# HALL_SENSOR_BOARD.net
KiCad netlist of a schematic drawn in Altium Designer
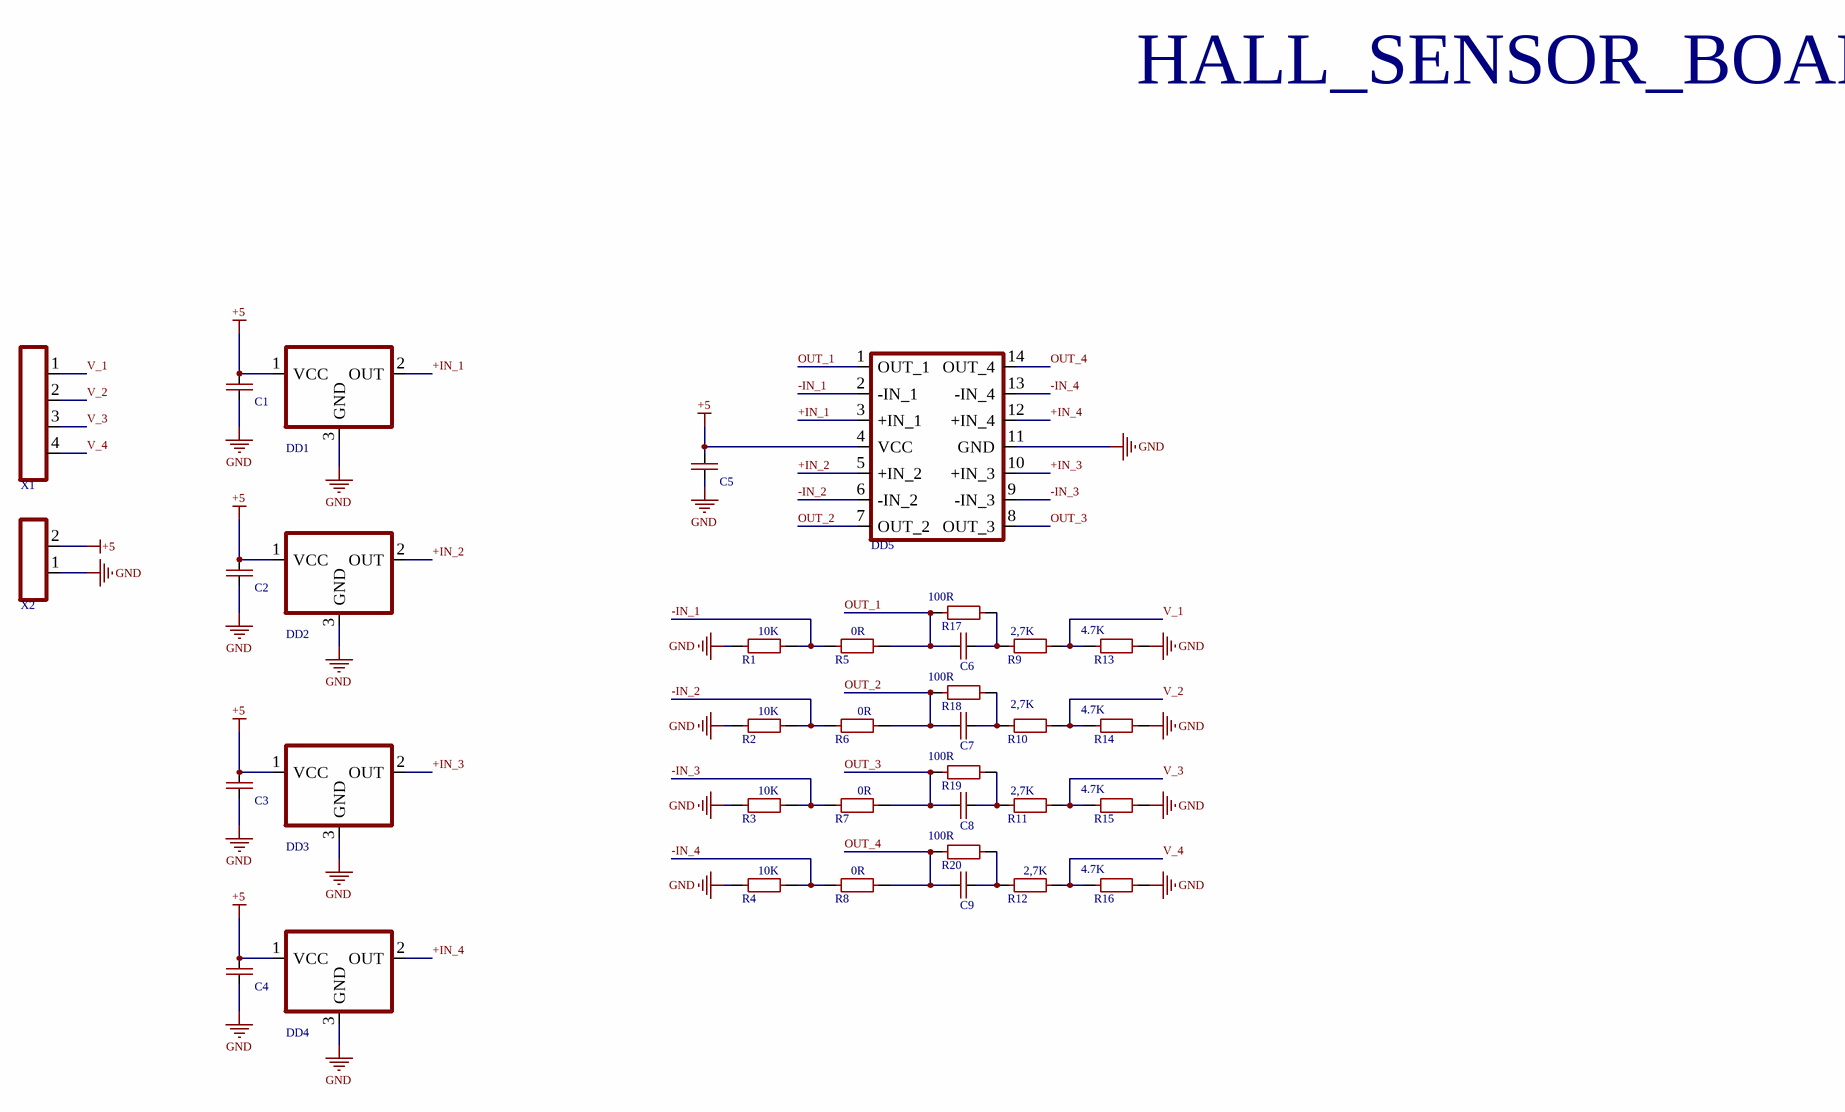
[diagram p0: HALL_SENSOR_BOARD.SchDoc]

(export (version "E")
  (design (tool "Eeschema 10.0.6"))
  (components
    (comp (ref "C1")
      (value "CAP-NON-POLAR")
      (footprint "CAP-0805")
      (libsource (lib "PASSIVE_COMPONENTS") (part "CAP-NON-POLAR"))
    )
    (comp (ref "C2")
      (value "CAP-NON-POLAR")
      (footprint "CAP-0805")
      (libsource (lib "PASSIVE_COMPONENTS") (part "CAP-NON-POLAR"))
    )
    (comp (ref "C3")
      (value "CAP-NON-POLAR")
      (footprint "CAP-0805")
      (libsource (lib "PASSIVE_COMPONENTS") (part "CAP-NON-POLAR"))
    )
    (comp (ref "C4")
      (value "CAP-NON-POLAR")
      (footprint "CAP-0805")
      (libsource (lib "PASSIVE_COMPONENTS") (part "CAP-NON-POLAR"))
    )
    (comp (ref "C5")
      (value "CAP-NON-POLAR")
      (footprint "CAP-0805")
      (libsource (lib "PASSIVE_COMPONENTS") (part "CAP-NON-POLAR"))
    )
    (comp (ref "C6")
      (value "CAP-NON-POLAR")
      (footprint "CAP-0805")
      (libsource (lib "PASSIVE_COMPONENTS") (part "CAP-NON-POLAR"))
    )
    (comp (ref "C7")
      (value "CAP-NON-POLAR")
      (footprint "CAP-0805")
      (libsource (lib "PASSIVE_COMPONENTS") (part "CAP-NON-POLAR"))
    )
    (comp (ref "C8")
      (value "CAP-NON-POLAR")
      (footprint "CAP-0805")
      (libsource (lib "PASSIVE_COMPONENTS") (part "CAP-NON-POLAR"))
    )
    (comp (ref "C9")
      (value "CAP-NON-POLAR")
      (footprint "CAP-0805")
      (libsource (lib "PASSIVE_COMPONENTS") (part "CAP-NON-POLAR"))
    )
    (comp (ref "DD1") (value "49E") (footprint "SOT23-3") (libsource (lib "49E") (part "49E")))
    (comp (ref "DD2") (value "49E") (footprint "SOT23-3") (libsource (lib "49E") (part "49E")))
    (comp (ref "DD3") (value "49E") (footprint "SOT23-3") (libsource (lib "49E") (part "49E")))
    (comp (ref "DD4") (value "49E") (footprint "SOT23-3") (libsource (lib "49E") (part "49E")))
    (comp (ref "DD5") (value "LM324") (footprint "SOIC14") (libsource (lib "LM324") (part "LM324")))
    (comp (ref "R1")
      (value "10K")
      (footprint "RES-0603")
      (libsource (lib "PASSIVE_COMPONENTS") (part "RES-CONST"))
    )
    (comp (ref "R2")
      (value "10K")
      (footprint "RES-0603")
      (libsource (lib "PASSIVE_COMPONENTS") (part "RES-CONST"))
    )
    (comp (ref "R3")
      (value "10K")
      (footprint "RES-0603")
      (libsource (lib "PASSIVE_COMPONENTS") (part "RES-CONST"))
    )
    (comp (ref "R4")
      (value "10K")
      (footprint "RES-0603")
      (libsource (lib "PASSIVE_COMPONENTS") (part "RES-CONST"))
    )
    (comp (ref "R5")
      (value "0R")
      (footprint "RES-0603")
      (libsource (lib "PASSIVE_COMPONENTS") (part "RES-CONST"))
    )
    (comp (ref "R6")
      (value "0R")
      (footprint "RES-0603")
      (libsource (lib "PASSIVE_COMPONENTS") (part "RES-CONST"))
    )
    (comp (ref "R7")
      (value "0R")
      (footprint "RES-0603")
      (libsource (lib "PASSIVE_COMPONENTS") (part "RES-CONST"))
    )
    (comp (ref "R8")
      (value "0R")
      (footprint "RES-0603")
      (libsource (lib "PASSIVE_COMPONENTS") (part "RES-CONST"))
    )
    (comp (ref "R9")
      (value "2,7K")
      (footprint "RES-0603")
      (libsource (lib "PASSIVE_COMPONENTS") (part "RES-CONST"))
    )
    (comp (ref "R10")
      (value "2,7K")
      (footprint "RES-0603")
      (libsource (lib "PASSIVE_COMPONENTS") (part "RES-CONST"))
    )
    (comp (ref "R11")
      (value "2,7K")
      (footprint "RES-0603")
      (libsource (lib "PASSIVE_COMPONENTS") (part "RES-CONST"))
    )
    (comp (ref "R12")
      (value "2,7K")
      (footprint "RES-0603")
      (libsource (lib "PASSIVE_COMPONENTS") (part "RES-CONST"))
    )
    (comp (ref "R13")
      (value "4.7K")
      (footprint "RES-0603")
      (libsource (lib "PASSIVE_COMPONENTS") (part "RES-CONST"))
    )
    (comp (ref "R14")
      (value "4.7K")
      (footprint "RES-0603")
      (libsource (lib "PASSIVE_COMPONENTS") (part "RES-CONST"))
    )
    (comp (ref "R15")
      (value "4.7K")
      (footprint "RES-0603")
      (libsource (lib "PASSIVE_COMPONENTS") (part "RES-CONST"))
    )
    (comp (ref "R16")
      (value "4.7K")
      (footprint "RES-0603")
      (libsource (lib "PASSIVE_COMPONENTS") (part "RES-CONST"))
    )
    (comp (ref "R17")
      (value "100R")
      (footprint "RES-0603")
      (libsource (lib "PASSIVE_COMPONENTS") (part "RES-CONST"))
    )
    (comp (ref "R18")
      (value "100R")
      (footprint "RES-0603")
      (libsource (lib "PASSIVE_COMPONENTS") (part "RES-CONST"))
    )
    (comp (ref "R19")
      (value "100R")
      (footprint "RES-0603")
      (libsource (lib "PASSIVE_COMPONENTS") (part "RES-CONST"))
    )
    (comp (ref "R20")
      (value "100R")
      (footprint "RES-0603")
      (libsource (lib "PASSIVE_COMPONENTS") (part "RES-CONST"))
    )
    (comp (ref "X1")
      (value "CONN-4-PIN")
      (footprint "CONN-PLS-4-2.54mm")
      (libsource (lib "CONNECTORS") (part "CONN-4-PIN"))
    )
    (comp (ref "X2")
      (value "CONN-2-PIN")
      (footprint "CONN-PLS-2-2.54mm")
      (libsource (lib "CONNECTORS") (part "CONN-2-PIN"))
    )
  )
  (nets
    (net (code "1") (name "+5") (class "Default")
      (node (ref "C1") (pin "2") (pinfunction "2_2") (pintype "passive"))
      (node (ref "C2") (pin "2") (pinfunction "2_2") (pintype "passive"))
      (node (ref "C3") (pin "2") (pinfunction "2_2") (pintype "passive"))
      (node (ref "C4") (pin "2") (pinfunction "2_2") (pintype "passive"))
      (node (ref "C5") (pin "2") (pinfunction "2_2") (pintype "passive"))
      (node (ref "DD1") (pin "1") (pinfunction "VCC_1") (pintype "passive"))
      (node (ref "DD2") (pin "1") (pinfunction "VCC_1") (pintype "passive"))
      (node (ref "DD3") (pin "1") (pinfunction "VCC_1") (pintype "passive"))
      (node (ref "DD4") (pin "1") (pinfunction "VCC_1") (pintype "passive"))
      (node (ref "DD5") (pin "4") (pinfunction "VCC_4") (pintype "passive"))
      (node (ref "X2") (pin "2") (pinfunction "2_2") (pintype "passive"))
    )
    (net (code "2") (name "/+IN_1") (class "Default")
      (node (ref "DD1") (pin "2") (pinfunction "OUT_2") (pintype "passive"))
      (node (ref "DD5") (pin "3") (pinfunction "+IN_1_3") (pintype "passive"))
    )
    (net (code "3") (name "/+IN_2") (class "Default")
      (node (ref "DD2") (pin "2") (pinfunction "OUT_2") (pintype "passive"))
      (node (ref "DD5") (pin "5") (pinfunction "+IN_2_5") (pintype "passive"))
    )
    (net (code "4") (name "/+IN_3") (class "Default")
      (node (ref "DD3") (pin "2") (pinfunction "OUT_2") (pintype "passive"))
      (node (ref "DD5") (pin "10") (pinfunction "+IN_3_10") (pintype "passive"))
    )
    (net (code "5") (name "/+IN_4") (class "Default")
      (node (ref "DD4") (pin "2") (pinfunction "OUT_2") (pintype "passive"))
      (node (ref "DD5") (pin "12") (pinfunction "+IN_4_12") (pintype "passive"))
    )
    (net (code "6") (name "/-IN_1") (class "Default")
      (node (ref "DD5") (pin "2") (pinfunction "-IN_1_2") (pintype "passive"))
      (node (ref "R1") (pin "2") (pinfunction "2_2") (pintype "passive"))
      (node (ref "R5") (pin "1") (pinfunction "1_1") (pintype "passive"))
    )
    (net (code "7") (name "/-IN_2") (class "Default")
      (node (ref "DD5") (pin "6") (pinfunction "-IN_2_6") (pintype "passive"))
      (node (ref "R2") (pin "2") (pinfunction "2_2") (pintype "passive"))
      (node (ref "R6") (pin "1") (pinfunction "1_1") (pintype "passive"))
    )
    (net (code "8") (name "/-IN_3") (class "Default")
      (node (ref "DD5") (pin "9") (pinfunction "-IN_3_9") (pintype "passive"))
      (node (ref "R3") (pin "2") (pinfunction "2_2") (pintype "passive"))
      (node (ref "R7") (pin "1") (pinfunction "1_1") (pintype "passive"))
    )
    (net (code "9") (name "/-IN_4") (class "Default")
      (node (ref "DD5") (pin "13") (pinfunction "-IN_4_13") (pintype "passive"))
      (node (ref "R4") (pin "2") (pinfunction "2_2") (pintype "passive"))
      (node (ref "R8") (pin "1") (pinfunction "1_1") (pintype "passive"))
    )
    (net (code "10") (name "/OUT_1") (class "Default")
      (node (ref "C6") (pin "2") (pinfunction "2_2") (pintype "passive"))
      (node (ref "DD5") (pin "1") (pinfunction "OUT_1_1") (pintype "passive"))
      (node (ref "R17") (pin "2") (pinfunction "2_2") (pintype "passive"))
      (node (ref "R5") (pin "2") (pinfunction "2_2") (pintype "passive"))
    )
    (net (code "11") (name "/OUT_2") (class "Default")
      (node (ref "C7") (pin "2") (pinfunction "2_2") (pintype "passive"))
      (node (ref "DD5") (pin "7") (pinfunction "OUT_2_7") (pintype "passive"))
      (node (ref "R18") (pin "2") (pinfunction "2_2") (pintype "passive"))
      (node (ref "R6") (pin "2") (pinfunction "2_2") (pintype "passive"))
    )
    (net (code "12") (name "/OUT_3") (class "Default")
      (node (ref "C8") (pin "2") (pinfunction "2_2") (pintype "passive"))
      (node (ref "DD5") (pin "8") (pinfunction "OUT_3_8") (pintype "passive"))
      (node (ref "R19") (pin "2") (pinfunction "2_2") (pintype "passive"))
      (node (ref "R7") (pin "2") (pinfunction "2_2") (pintype "passive"))
    )
    (net (code "13") (name "/OUT_4") (class "Default")
      (node (ref "C9") (pin "2") (pinfunction "2_2") (pintype "passive"))
      (node (ref "DD5") (pin "14") (pinfunction "OUT_4_14") (pintype "passive"))
      (node (ref "R20") (pin "2") (pinfunction "2_2") (pintype "passive"))
      (node (ref "R8") (pin "2") (pinfunction "2_2") (pintype "passive"))
    )
    (net (code "14") (name "/V_1") (class "Default")
      (node (ref "R13") (pin "2") (pinfunction "2_2") (pintype "passive"))
      (node (ref "R9") (pin "1") (pinfunction "1_1") (pintype "passive"))
      (node (ref "X1") (pin "1") (pinfunction "1_1") (pintype "passive"))
    )
    (net (code "15") (name "/V_2") (class "Default")
      (node (ref "R10") (pin "1") (pinfunction "1_1") (pintype "passive"))
      (node (ref "R14") (pin "2") (pinfunction "2_2") (pintype "passive"))
      (node (ref "X1") (pin "2") (pinfunction "2_2") (pintype "passive"))
    )
    (net (code "16") (name "/V_3") (class "Default")
      (node (ref "R11") (pin "1") (pinfunction "1_1") (pintype "passive"))
      (node (ref "R15") (pin "2") (pinfunction "2_2") (pintype "passive"))
      (node (ref "X1") (pin "3") (pinfunction "3_3") (pintype "passive"))
    )
    (net (code "17") (name "/V_4") (class "Default")
      (node (ref "R12") (pin "1") (pinfunction "1_1") (pintype "passive"))
      (node (ref "R16") (pin "2") (pinfunction "2_2") (pintype "passive"))
      (node (ref "X1") (pin "4") (pinfunction "4_4") (pintype "passive"))
    )
    (net (code "18") (name "GND") (class "Default")
      (node (ref "C1") (pin "1") (pinfunction "1_1") (pintype "passive"))
      (node (ref "C2") (pin "1") (pinfunction "1_1") (pintype "passive"))
      (node (ref "C3") (pin "1") (pinfunction "1_1") (pintype "passive"))
      (node (ref "C4") (pin "1") (pinfunction "1_1") (pintype "passive"))
      (node (ref "C5") (pin "1") (pinfunction "1_1") (pintype "passive"))
      (node (ref "DD1") (pin "3") (pinfunction "GND_3") (pintype "passive"))
      (node (ref "DD2") (pin "3") (pinfunction "GND_3") (pintype "passive"))
      (node (ref "DD3") (pin "3") (pinfunction "GND_3") (pintype "passive"))
      (node (ref "DD4") (pin "3") (pinfunction "GND_3") (pintype "passive"))
      (node (ref "DD5") (pin "11") (pinfunction "GND_11") (pintype "passive"))
      (node (ref "R1") (pin "1") (pinfunction "1_1") (pintype "passive"))
      (node (ref "R13") (pin "1") (pinfunction "1_1") (pintype "passive"))
      (node (ref "R14") (pin "1") (pinfunction "1_1") (pintype "passive"))
      (node (ref "R15") (pin "1") (pinfunction "1_1") (pintype "passive"))
      (node (ref "R16") (pin "1") (pinfunction "1_1") (pintype "passive"))
      (node (ref "R2") (pin "1") (pinfunction "1_1") (pintype "passive"))
      (node (ref "R3") (pin "1") (pinfunction "1_1") (pintype "passive"))
      (node (ref "R4") (pin "1") (pinfunction "1_1") (pintype "passive"))
      (node (ref "X2") (pin "1") (pinfunction "1_1") (pintype "passive"))
    )
    (net (code "19") (name "Net-(C6-Pad1)") (class "Default")
      (node (ref "C6") (pin "1") (pinfunction "1_1") (pintype "passive"))
      (node (ref "R17") (pin "1") (pinfunction "1_1") (pintype "passive"))
      (node (ref "R9") (pin "2") (pinfunction "2_2") (pintype "passive"))
    )
    (net (code "20") (name "Net-(C7-Pad1)") (class "Default")
      (node (ref "C7") (pin "1") (pinfunction "1_1") (pintype "passive"))
      (node (ref "R10") (pin "2") (pinfunction "2_2") (pintype "passive"))
      (node (ref "R18") (pin "1") (pinfunction "1_1") (pintype "passive"))
    )
    (net (code "21") (name "Net-(C8-Pad1)") (class "Default")
      (node (ref "C8") (pin "1") (pinfunction "1_1") (pintype "passive"))
      (node (ref "R11") (pin "2") (pinfunction "2_2") (pintype "passive"))
      (node (ref "R19") (pin "1") (pinfunction "1_1") (pintype "passive"))
    )
    (net (code "22") (name "Net-(C9-Pad1)") (class "Default")
      (node (ref "C9") (pin "1") (pinfunction "1_1") (pintype "passive"))
      (node (ref "R12") (pin "2") (pinfunction "2_2") (pintype "passive"))
      (node (ref "R20") (pin "1") (pinfunction "1_1") (pintype "passive"))
    )
  )
)
